# c12880ma.net
KiCad netlist of a schematic drawn in EAGLE
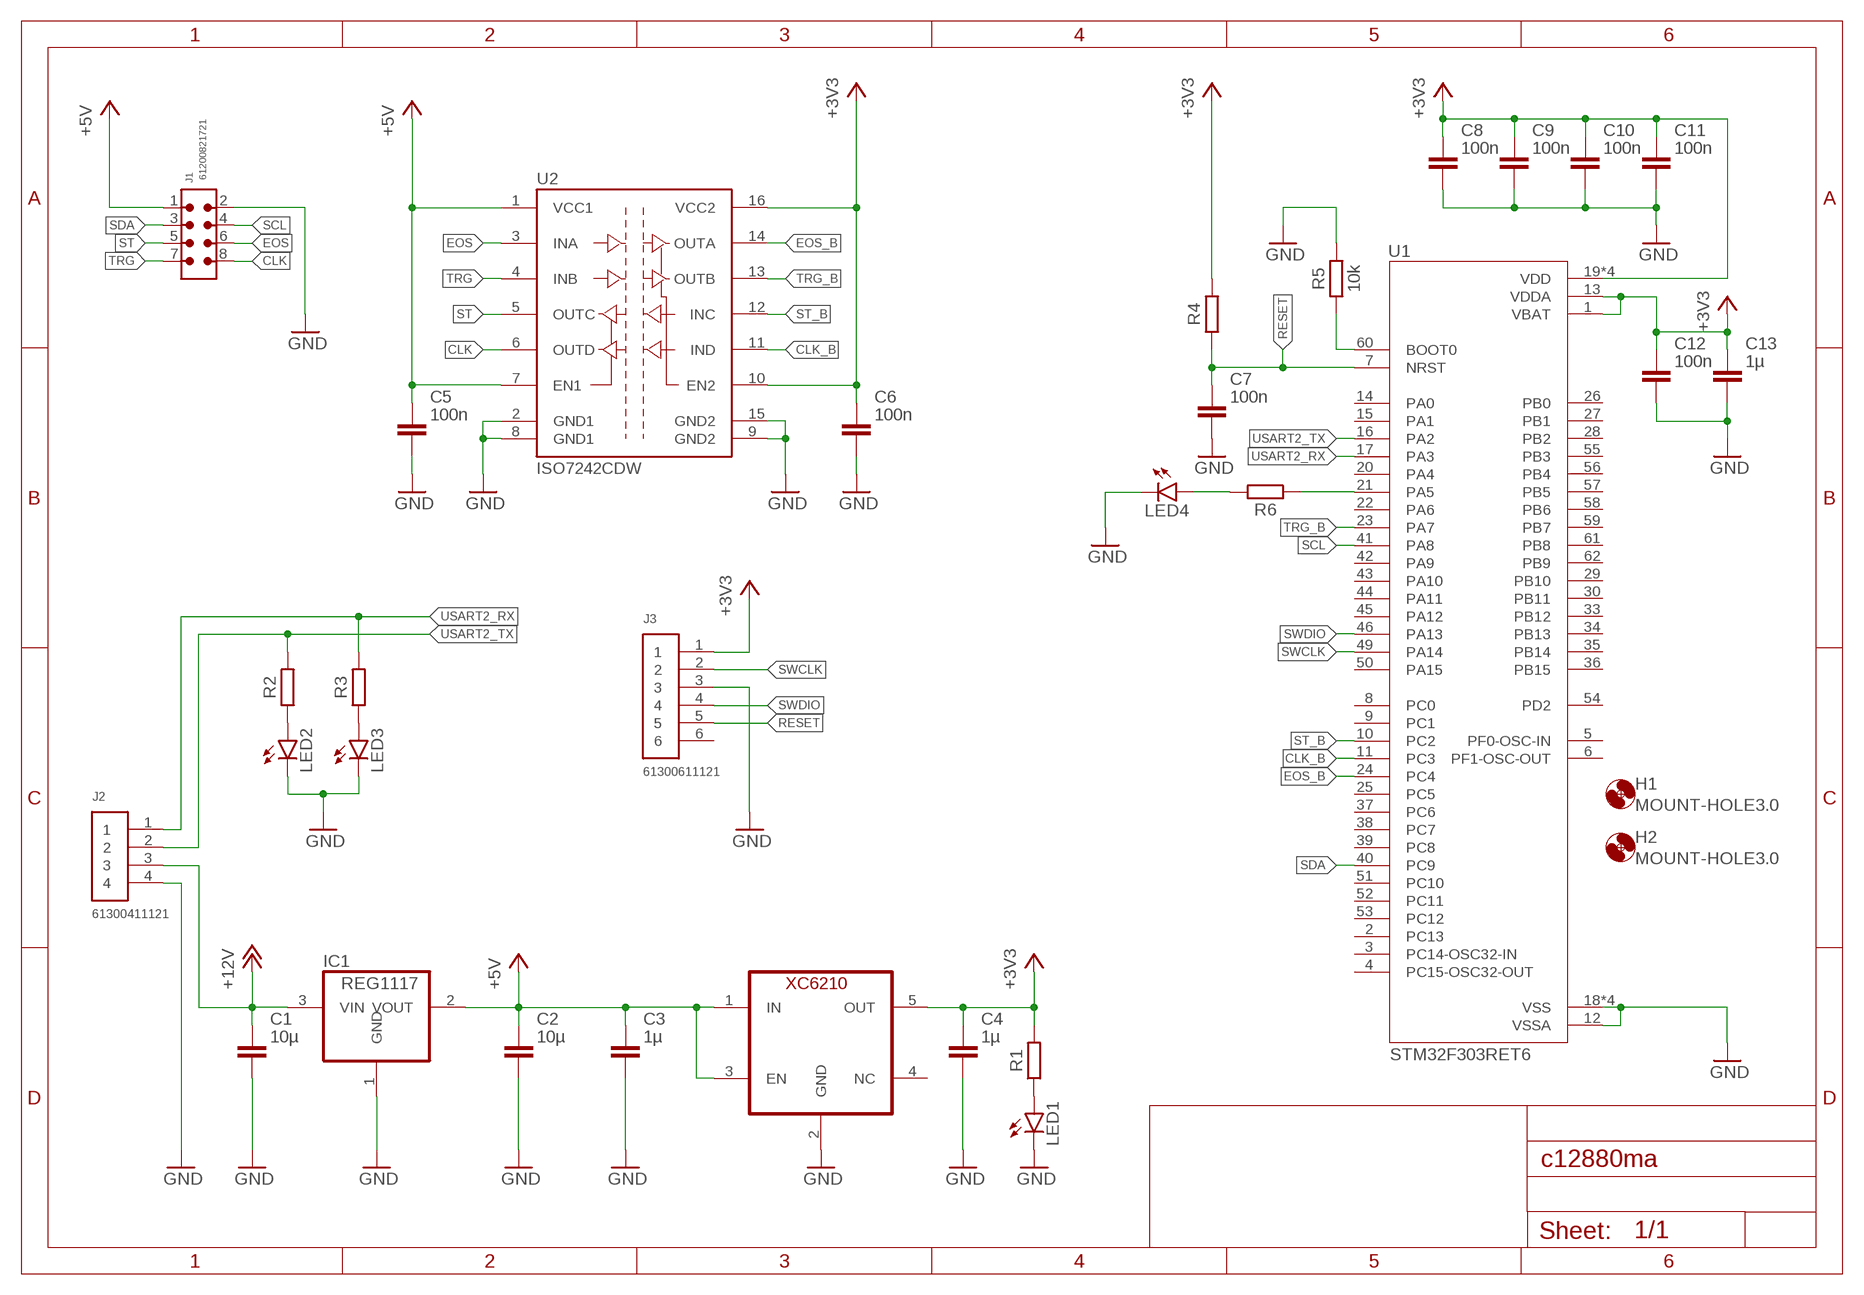
[diagram p0: schematic, sheet 1]

(export (version "E")
  (design (tool "Eeschema 10.0.6"))
  (components
    (comp (ref "C1")
      (value "10µ")
      (footprint "eagle-import:CAPC1608X85")
      (libsource (lib "eagle-import") (part "CCHIP-0603(1608-METRIC)_"))
    )
    (comp (ref "C2")
      (value "10µ")
      (footprint "eagle-import:CAPC1608X85")
      (libsource (lib "eagle-import") (part "CCHIP-0603(1608-METRIC)_"))
    )
    (comp (ref "C3")
      (value "1µ")
      (footprint "eagle-import:CAPC1608X85")
      (libsource (lib "eagle-import") (part "CCHIP-0603(1608-METRIC)_"))
    )
    (comp (ref "C4")
      (value "1µ")
      (footprint "eagle-import:CAPC1608X85")
      (libsource (lib "eagle-import") (part "CCHIP-0603(1608-METRIC)_"))
    )
    (comp (ref "C5")
      (value "100n")
      (footprint "eagle-import:CAPC1608X85")
      (libsource (lib "eagle-import") (part "CCHIP-0603(1608-METRIC)_"))
    )
    (comp (ref "C6")
      (value "100n")
      (footprint "eagle-import:CAPC1608X85")
      (libsource (lib "eagle-import") (part "CCHIP-0603(1608-METRIC)_"))
    )
    (comp (ref "C7")
      (value "100n")
      (footprint "eagle-import:CAPC1608X85")
      (libsource (lib "eagle-import") (part "CCHIP-0603(1608-METRIC)_"))
    )
    (comp (ref "C8")
      (value "100n")
      (footprint "eagle-import:CAPC1608X85")
      (libsource (lib "eagle-import") (part "CCHIP-0603(1608-METRIC)_"))
    )
    (comp (ref "C9")
      (value "100n")
      (footprint "eagle-import:CAPC1608X85")
      (libsource (lib "eagle-import") (part "CCHIP-0603(1608-METRIC)_"))
    )
    (comp (ref "C10")
      (value "100n")
      (footprint "eagle-import:CAPC1608X85")
      (libsource (lib "eagle-import") (part "CCHIP-0603(1608-METRIC)_"))
    )
    (comp (ref "C11")
      (value "100n")
      (footprint "eagle-import:CAPC1608X85")
      (libsource (lib "eagle-import") (part "CCHIP-0603(1608-METRIC)_"))
    )
    (comp (ref "C12")
      (value "100n")
      (footprint "eagle-import:CAPC1608X85")
      (libsource (lib "eagle-import") (part "CCHIP-0603(1608-METRIC)_"))
    )
    (comp (ref "C13")
      (value "1µ")
      (footprint "eagle-import:CAPC1608X85")
      (libsource (lib "eagle-import") (part "CCHIP-0603(1608-METRIC)_"))
    )
    (comp (ref "H1")
      (value "MOUNT-HOLE3.0")
      (footprint "eagle-import:3,0")
      (libsource (lib "eagle-import") (part "MOUNT-HOLE3.0"))
    )
    (comp (ref "H2")
      (value "MOUNT-HOLE3.0")
      (footprint "eagle-import:3,0")
      (libsource (lib "eagle-import") (part "MOUNT-HOLE3.0"))
    )
    (comp (ref "IC1")
      (value "REG1117")
      (footprint "eagle-import:SOT223")
      (libsource (lib "eagle-import") (part "REG1117"))
    )
    (comp (ref "J1")
      (value "61200821721")
      (footprint "eagle-import:61200821721")
      (libsource (lib "eagle-import") (part "6120XX21721_61200821721"))
    )
    (comp (ref "J2")
      (value "61300411121")
      (footprint "eagle-import:61300411121")
      (fields
        (field (name "DIGI_KEY_PART_NUMBER") "732-5317-ND")
        (field (name "MANUFACTURER") "Wurth Electronics Inc.")
        (field (name "CREATED_BY") "PCBLayout.com")
      )
      (libsource (lib "eagle-import") (part "61300411121"))
    )
    (comp (ref "J3")
      (value "61300611121")
      (footprint "eagle-import:61300611121")
      (fields
        (field (name "DIGI_KEY_PART_NUMBER") "732-5319-ND")
        (field (name "MANUFACTURER") "Wurth Electronics Inc.")
        (field (name "CREATED_BY") "PCBLayout.com")
      )
      (libsource (lib "eagle-import") (part "61300611121"))
    )
    (comp (ref "LED1")
      (value "LEDCHIP-LED0603")
      (footprint "eagle-import:CHIP-LED0603")
      (libsource (lib "eagle-import") (part "LEDCHIP-LED0603"))
    )
    (comp (ref "LED2")
      (value "LEDCHIP-LED0603")
      (footprint "eagle-import:CHIP-LED0603")
      (libsource (lib "eagle-import") (part "LEDCHIP-LED0603"))
    )
    (comp (ref "LED3")
      (value "LEDCHIP-LED0603")
      (footprint "eagle-import:CHIP-LED0603")
      (libsource (lib "eagle-import") (part "LEDCHIP-LED0603"))
    )
    (comp (ref "LED4")
      (value "LEDCHIP-LED0603")
      (footprint "eagle-import:CHIP-LED0603")
      (libsource (lib "eagle-import") (part "LEDCHIP-LED0603"))
    )
    (comp (ref "R1")
      (value "R_CHIP-0603(1608-METRIC)")
      (footprint "eagle-import:RESC1608X60")
      (libsource (lib "eagle-import") (part "RCHIP-0603(1608-METRIC)_"))
    )
    (comp (ref "R2")
      (value "R_CHIP-0603(1608-METRIC)")
      (footprint "eagle-import:RESC1608X60")
      (libsource (lib "eagle-import") (part "RCHIP-0603(1608-METRIC)_"))
    )
    (comp (ref "R3")
      (value "R_CHIP-0603(1608-METRIC)")
      (footprint "eagle-import:RESC1608X60")
      (libsource (lib "eagle-import") (part "RCHIP-0603(1608-METRIC)_"))
    )
    (comp (ref "R4")
      (value "R_CHIP-0603(1608-METRIC)")
      (footprint "eagle-import:RESC1608X60")
      (libsource (lib "eagle-import") (part "RCHIP-0603(1608-METRIC)_"))
    )
    (comp (ref "R5")
      (value "10k")
      (footprint "eagle-import:RESC1608X60")
      (libsource (lib "eagle-import") (part "RCHIP-0603(1608-METRIC)_"))
    )
    (comp (ref "R6")
      (value "R_CHIP-0603(1608-METRIC)")
      (footprint "eagle-import:RESC1608X60")
      (libsource (lib "eagle-import") (part "RCHIP-0603(1608-METRIC)_"))
    )
    (comp (ref "U$1")
      (value "XC6210")
      (footprint "eagle-import:SOT23-5")
      (libsource (lib "eagle-import") (part "XC6210"))
    )
    (comp (ref "U1")
      (value "STM32F303RET6")
      (footprint "eagle-import:QFP50P1200X1200X160-64N")
      (fields (field (name "MF") "STMicroelectronics"))
      (libsource (lib "eagle-import") (part "STM32F303RET6"))
    )
    (comp (ref "U2")
      (value "ISO7242CDW")
      (footprint "eagle-import:SO-16DW")
      (libsource (lib "eagle-import") (part "ISO7242DWC"))
    )
  )
  (nets
    (net (code "1") (name "+3V3") (class "Default")
      (node (ref "C10") (pin "1") (pinfunction "1_1") (pintype "passive"))
      (node (ref "C11") (pin "1") (pinfunction "1_1") (pintype "passive"))
      (node (ref "C12") (pin "1") (pinfunction "1_1") (pintype "passive"))
      (node (ref "C13") (pin "1") (pinfunction "1_1") (pintype "passive"))
      (node (ref "C4") (pin "1") (pinfunction "1_1") (pintype "passive"))
      (node (ref "C6") (pin "1") (pinfunction "1_1") (pintype "passive"))
      (node (ref "C8") (pin "1") (pinfunction "1_1") (pintype "passive"))
      (node (ref "C9") (pin "1") (pinfunction "1_1") (pintype "passive"))
      (node (ref "J3") (pin "1") (pinfunction "1_1") (pintype "passive"))
      (node (ref "R1") (pin "2") (pinfunction "2_2") (pintype "passive"))
      (node (ref "R4") (pin "2") (pinfunction "2_2") (pintype "passive"))
      (node (ref "U$1") (pin "5") (pinfunction "OUT_5") (pintype "bidirectional"))
      (node (ref "U1") (pin "1") (pinfunction "VBAT_1") (pintype "power_in"))
      (node (ref "U1") (pin "13") (pinfunction "VDDA_13") (pintype "power_in"))
      (node (ref "U1") (pin "19") (pinfunction "VDD_19") (pintype "power_in"))
      (node (ref "U1") (pin "32") (pinfunction "VDD_32") (pintype "power_in"))
      (node (ref "U1") (pin "48") (pinfunction "VDD_48") (pintype "power_in"))
      (node (ref "U1") (pin "64") (pinfunction "VDD_64") (pintype "power_in"))
      (node (ref "U2") (pin "10") (pinfunction "EN2_10") (pintype "passive"))
      (node (ref "U2") (pin "16") (pinfunction "VCC2_16") (pintype "power_in"))
    )
    (net (code "2") (name "+5V") (class "Default")
      (node (ref "C2") (pin "1") (pinfunction "1_1") (pintype "passive"))
      (node (ref "C3") (pin "1") (pinfunction "1_1") (pintype "passive"))
      (node (ref "C5") (pin "1") (pinfunction "1_1") (pintype "passive"))
      (node (ref "IC1") (pin "2") (pinfunction "VOUT_2") (pintype "output"))
      (node (ref "J1") (pin "1") (pinfunction "1_1") (pintype "passive"))
      (node (ref "U$1") (pin "1") (pinfunction "IN_1") (pintype "bidirectional"))
      (node (ref "U$1") (pin "3") (pinfunction "EN_3") (pintype "bidirectional"))
      (node (ref "U2") (pin "1") (pinfunction "VCC1_1") (pintype "power_in"))
      (node (ref "U2") (pin "7") (pinfunction "EN1_7") (pintype "passive"))
    )
    (net (code "3") (name "+12V") (class "Default")
      (node (ref "C1") (pin "1") (pinfunction "1_1") (pintype "passive"))
      (node (ref "IC1") (pin "3") (pinfunction "VIN_3") (pintype "input"))
      (node (ref "J2") (pin "3") (pinfunction "3_3") (pintype "passive"))
    )
    (net (code "4") (name "CLK") (class "Default")
      (node (ref "J1") (pin "8") (pinfunction "8_8") (pintype "passive"))
      (node (ref "U2") (pin "6") (pinfunction "OUTD_6") (pintype "tri_state"))
    )
    (net (code "5") (name "CLK_B") (class "Default")
      (node (ref "U1") (pin "11") (pinfunction "PC3_11") (pintype "bidirectional"))
      (node (ref "U2") (pin "11") (pinfunction "IND_11") (pintype "passive"))
    )
    (net (code "6") (name "EOS") (class "Default")
      (node (ref "J1") (pin "6") (pinfunction "6_6") (pintype "passive"))
      (node (ref "U2") (pin "3") (pinfunction "INA_3") (pintype "passive"))
    )
    (net (code "7") (name "EOS_B") (class "Default")
      (node (ref "U1") (pin "24") (pinfunction "PC4_24") (pintype "bidirectional"))
      (node (ref "U2") (pin "14") (pinfunction "OUTA_14") (pintype "tri_state"))
    )
    (net (code "8") (name "GND") (class "Default")
      (node (ref "C1") (pin "2") (pinfunction "2_2") (pintype "passive"))
      (node (ref "C10") (pin "2") (pinfunction "2_2") (pintype "passive"))
      (node (ref "C11") (pin "2") (pinfunction "2_2") (pintype "passive"))
      (node (ref "C12") (pin "2") (pinfunction "2_2") (pintype "passive"))
      (node (ref "C13") (pin "2") (pinfunction "2_2") (pintype "passive"))
      (node (ref "C2") (pin "2") (pinfunction "2_2") (pintype "passive"))
      (node (ref "C3") (pin "2") (pinfunction "2_2") (pintype "passive"))
      (node (ref "C4") (pin "2") (pinfunction "2_2") (pintype "passive"))
      (node (ref "C5") (pin "2") (pinfunction "2_2") (pintype "passive"))
      (node (ref "C6") (pin "2") (pinfunction "2_2") (pintype "passive"))
      (node (ref "C7") (pin "2") (pinfunction "2_2") (pintype "passive"))
      (node (ref "C8") (pin "2") (pinfunction "2_2") (pintype "passive"))
      (node (ref "C9") (pin "2") (pinfunction "2_2") (pintype "passive"))
      (node (ref "IC1") (pin "1") (pinfunction "GND_1") (pintype "power_in"))
      (node (ref "J1") (pin "2") (pinfunction "2_2") (pintype "passive"))
      (node (ref "J2") (pin "4") (pinfunction "4_4") (pintype "passive"))
      (node (ref "J3") (pin "3") (pinfunction "3_3") (pintype "passive"))
      (node (ref "LED1") (pin "C") (pinfunction "C_C") (pintype "passive"))
      (node (ref "LED2") (pin "C") (pinfunction "C_C") (pintype "passive"))
      (node (ref "LED3") (pin "C") (pinfunction "C_C") (pintype "passive"))
      (node (ref "LED4") (pin "C") (pinfunction "C_C") (pintype "passive"))
      (node (ref "R5") (pin "2") (pinfunction "2_2") (pintype "passive"))
      (node (ref "U$1") (pin "2") (pinfunction "GND_2") (pintype "bidirectional"))
      (node (ref "U1") (pin "12") (pinfunction "VSSA_12") (pintype "power_in"))
      (node (ref "U1") (pin "18") (pinfunction "VSS_18") (pintype "power_in"))
      (node (ref "U1") (pin "31") (pinfunction "VSS_31") (pintype "power_in"))
      (node (ref "U1") (pin "47") (pinfunction "VSS_47") (pintype "power_in"))
      (node (ref "U1") (pin "63") (pinfunction "VSS_63") (pintype "power_in"))
      (node (ref "U2") (pin "15") (pinfunction "GND2_15") (pintype "power_in"))
      (node (ref "U2") (pin "2") (pinfunction "GND1_2") (pintype "power_in"))
      (node (ref "U2") (pin "8") (pinfunction "GND1_8") (pintype "power_in"))
      (node (ref "U2") (pin "9") (pinfunction "GND2_9") (pintype "power_in"))
    )
    (net (code "9") (name "Net-(LED1-PadA)") (class "Default")
      (node (ref "LED1") (pin "A") (pinfunction "A_A") (pintype "passive"))
      (node (ref "R1") (pin "1") (pinfunction "1_1") (pintype "passive"))
    )
    (net (code "10") (name "Net-(LED2-PadA)") (class "Default")
      (node (ref "LED2") (pin "A") (pinfunction "A_A") (pintype "passive"))
      (node (ref "R2") (pin "1") (pinfunction "1_1") (pintype "passive"))
    )
    (net (code "11") (name "Net-(LED3-PadA)") (class "Default")
      (node (ref "LED3") (pin "A") (pinfunction "A_A") (pintype "passive"))
      (node (ref "R3") (pin "1") (pinfunction "1_1") (pintype "passive"))
    )
    (net (code "12") (name "Net-(LED4-PadA)") (class "Default")
      (node (ref "LED4") (pin "A") (pinfunction "A_A") (pintype "passive"))
      (node (ref "R6") (pin "2") (pinfunction "2_2") (pintype "passive"))
    )
    (net (code "13") (name "Net-(U1-BOOT0)") (class "Default")
      (node (ref "R5") (pin "1") (pinfunction "1_1") (pintype "passive"))
      (node (ref "U1") (pin "60") (pinfunction "BOOT0_60") (pintype "input"))
    )
    (net (code "14") (name "Net-(U1-PA5)") (class "Default")
      (node (ref "R6") (pin "1") (pinfunction "1_1") (pintype "passive"))
      (node (ref "U1") (pin "21") (pinfunction "PA5_21") (pintype "bidirectional"))
    )
    (net (code "15") (name "RESET") (class "Default")
      (node (ref "C7") (pin "1") (pinfunction "1_1") (pintype "passive"))
      (node (ref "J3") (pin "5") (pinfunction "5_5") (pintype "passive"))
      (node (ref "R4") (pin "1") (pinfunction "1_1") (pintype "passive"))
      (node (ref "U1") (pin "7") (pinfunction "NRST_7") (pintype "bidirectional"))
    )
    (net (code "16") (name "SCL") (class "Default")
      (node (ref "J1") (pin "4") (pinfunction "4_4") (pintype "passive"))
      (node (ref "U1") (pin "41") (pinfunction "PA8_41") (pintype "bidirectional"))
    )
    (net (code "17") (name "SDA") (class "Default")
      (node (ref "J1") (pin "3") (pinfunction "3_3") (pintype "passive"))
      (node (ref "U1") (pin "40") (pinfunction "PC9_40") (pintype "bidirectional"))
    )
    (net (code "18") (name "ST") (class "Default")
      (node (ref "J1") (pin "5") (pinfunction "5_5") (pintype "passive"))
      (node (ref "U2") (pin "5") (pinfunction "OUTC_5") (pintype "tri_state"))
    )
    (net (code "19") (name "ST_B") (class "Default")
      (node (ref "U1") (pin "10") (pinfunction "PC2_10") (pintype "bidirectional"))
      (node (ref "U2") (pin "12") (pinfunction "INC_12") (pintype "passive"))
    )
    (net (code "20") (name "SWCLK") (class "Default")
      (node (ref "J3") (pin "2") (pinfunction "2_2") (pintype "passive"))
      (node (ref "U1") (pin "49") (pinfunction "PA14_49") (pintype "bidirectional"))
    )
    (net (code "21") (name "SWDIO") (class "Default")
      (node (ref "J3") (pin "4") (pinfunction "4_4") (pintype "passive"))
      (node (ref "U1") (pin "46") (pinfunction "PA13_46") (pintype "bidirectional"))
    )
    (net (code "22") (name "TRG") (class "Default")
      (node (ref "J1") (pin "7") (pinfunction "7_7") (pintype "passive"))
      (node (ref "U2") (pin "4") (pinfunction "INB_4") (pintype "passive"))
    )
    (net (code "23") (name "TRG_B") (class "Default")
      (node (ref "U1") (pin "23") (pinfunction "PA7_23") (pintype "bidirectional"))
      (node (ref "U2") (pin "13") (pinfunction "OUTB_13") (pintype "tri_state"))
    )
    (net (code "24") (name "USART2_RX") (class "Default")
      (node (ref "J2") (pin "1") (pinfunction "1_1") (pintype "passive"))
      (node (ref "R3") (pin "2") (pinfunction "2_2") (pintype "passive"))
      (node (ref "U1") (pin "17") (pinfunction "PA3_17") (pintype "bidirectional"))
    )
    (net (code "25") (name "USART2_TX") (class "Default")
      (node (ref "J2") (pin "2") (pinfunction "2_2") (pintype "passive"))
      (node (ref "R2") (pin "2") (pinfunction "2_2") (pintype "passive"))
      (node (ref "U1") (pin "16") (pinfunction "PA2_16") (pintype "bidirectional"))
    )
    (net (code "26") (name "unconnected-(J3-Pad6)") (class "Default")
      (node (ref "J3") (pin "6") (pinfunction "6_6") (pintype "passive"))
    )
    (net (code "27") (name "unconnected-(U$1-NC-Pad4)") (class "Default")
      (node (ref "U$1") (pin "4") (pinfunction "NC_4") (pintype "bidirectional"))
    )
    (net (code "28") (name "unconnected-(U1-PA0-Pad14)") (class "Default")
      (node (ref "U1") (pin "14") (pinfunction "PA0_14") (pintype "bidirectional"))
    )
    (net (code "29") (name "unconnected-(U1-PA1-Pad15)") (class "Default")
      (node (ref "U1") (pin "15") (pinfunction "PA1_15") (pintype "bidirectional"))
    )
    (net (code "30") (name "unconnected-(U1-PA4-Pad20)") (class "Default")
      (node (ref "U1") (pin "20") (pinfunction "PA4_20") (pintype "bidirectional"))
    )
    (net (code "31") (name "unconnected-(U1-PA6-Pad22)") (class "Default")
      (node (ref "U1") (pin "22") (pinfunction "PA6_22") (pintype "bidirectional"))
    )
    (net (code "32") (name "unconnected-(U1-PA9-Pad42)") (class "Default")
      (node (ref "U1") (pin "42") (pinfunction "PA9_42") (pintype "bidirectional"))
    )
    (net (code "33") (name "unconnected-(U1-PA10-Pad43)") (class "Default")
      (node (ref "U1") (pin "43") (pinfunction "PA10_43") (pintype "bidirectional"))
    )
    (net (code "34") (name "unconnected-(U1-PA11-Pad44)") (class "Default")
      (node (ref "U1") (pin "44") (pinfunction "PA11_44") (pintype "bidirectional"))
    )
    (net (code "35") (name "unconnected-(U1-PA12-Pad45)") (class "Default")
      (node (ref "U1") (pin "45") (pinfunction "PA12_45") (pintype "bidirectional"))
    )
    (net (code "36") (name "unconnected-(U1-PA15-Pad50)") (class "Default")
      (node (ref "U1") (pin "50") (pinfunction "PA15_50") (pintype "bidirectional"))
    )
    (net (code "37") (name "unconnected-(U1-PB0-Pad26)") (class "Default")
      (node (ref "U1") (pin "26") (pinfunction "PB0_26") (pintype "bidirectional"))
    )
    (net (code "38") (name "unconnected-(U1-PB1-Pad27)") (class "Default")
      (node (ref "U1") (pin "27") (pinfunction "PB1_27") (pintype "bidirectional"))
    )
    (net (code "39") (name "unconnected-(U1-PB2-Pad28)") (class "Default")
      (node (ref "U1") (pin "28") (pinfunction "PB2_28") (pintype "bidirectional"))
    )
    (net (code "40") (name "unconnected-(U1-PB3-Pad55)") (class "Default")
      (node (ref "U1") (pin "55") (pinfunction "PB3_55") (pintype "bidirectional"))
    )
    (net (code "41") (name "unconnected-(U1-PB4-Pad56)") (class "Default")
      (node (ref "U1") (pin "56") (pinfunction "PB4_56") (pintype "bidirectional"))
    )
    (net (code "42") (name "unconnected-(U1-PB5-Pad57)") (class "Default")
      (node (ref "U1") (pin "57") (pinfunction "PB5_57") (pintype "bidirectional"))
    )
    (net (code "43") (name "unconnected-(U1-PB6-Pad58)") (class "Default")
      (node (ref "U1") (pin "58") (pinfunction "PB6_58") (pintype "bidirectional"))
    )
    (net (code "44") (name "unconnected-(U1-PB7-Pad59)") (class "Default")
      (node (ref "U1") (pin "59") (pinfunction "PB7_59") (pintype "bidirectional"))
    )
    (net (code "45") (name "unconnected-(U1-PB8-Pad61)") (class "Default")
      (node (ref "U1") (pin "61") (pinfunction "PB8_61") (pintype "bidirectional"))
    )
    (net (code "46") (name "unconnected-(U1-PB9-Pad62)") (class "Default")
      (node (ref "U1") (pin "62") (pinfunction "PB9_62") (pintype "bidirectional"))
    )
    (net (code "47") (name "unconnected-(U1-PB10-Pad29)") (class "Default")
      (node (ref "U1") (pin "29") (pinfunction "PB10_29") (pintype "bidirectional"))
    )
    (net (code "48") (name "unconnected-(U1-PB11-Pad30)") (class "Default")
      (node (ref "U1") (pin "30") (pinfunction "PB11_30") (pintype "bidirectional"))
    )
    (net (code "49") (name "unconnected-(U1-PB12-Pad33)") (class "Default")
      (node (ref "U1") (pin "33") (pinfunction "PB12_33") (pintype "bidirectional"))
    )
    (net (code "50") (name "unconnected-(U1-PB13-Pad34)") (class "Default")
      (node (ref "U1") (pin "34") (pinfunction "PB13_34") (pintype "bidirectional"))
    )
    (net (code "51") (name "unconnected-(U1-PB14-Pad35)") (class "Default")
      (node (ref "U1") (pin "35") (pinfunction "PB14_35") (pintype "bidirectional"))
    )
    (net (code "52") (name "unconnected-(U1-PB15-Pad36)") (class "Default")
      (node (ref "U1") (pin "36") (pinfunction "PB15_36") (pintype "bidirectional"))
    )
    (net (code "53") (name "unconnected-(U1-PC0-Pad8)") (class "Default")
      (node (ref "U1") (pin "8") (pinfunction "PC0_8") (pintype "bidirectional"))
    )
    (net (code "54") (name "unconnected-(U1-PC1-Pad9)") (class "Default")
      (node (ref "U1") (pin "9") (pinfunction "PC1_9") (pintype "bidirectional"))
    )
    (net (code "55") (name "unconnected-(U1-PC5-Pad25)") (class "Default")
      (node (ref "U1") (pin "25") (pinfunction "PC5_25") (pintype "bidirectional"))
    )
    (net (code "56") (name "unconnected-(U1-PC6-Pad37)") (class "Default")
      (node (ref "U1") (pin "37") (pinfunction "PC6_37") (pintype "bidirectional"))
    )
    (net (code "57") (name "unconnected-(U1-PC7-Pad38)") (class "Default")
      (node (ref "U1") (pin "38") (pinfunction "PC7_38") (pintype "bidirectional"))
    )
    (net (code "58") (name "unconnected-(U1-PC8-Pad39)") (class "Default")
      (node (ref "U1") (pin "39") (pinfunction "PC8_39") (pintype "bidirectional"))
    )
    (net (code "59") (name "unconnected-(U1-PC10-Pad51)") (class "Default")
      (node (ref "U1") (pin "51") (pinfunction "PC10_51") (pintype "bidirectional"))
    )
    (net (code "60") (name "unconnected-(U1-PC11-Pad52)") (class "Default")
      (node (ref "U1") (pin "52") (pinfunction "PC11_52") (pintype "bidirectional"))
    )
    (net (code "61") (name "unconnected-(U1-PC12-Pad53)") (class "Default")
      (node (ref "U1") (pin "53") (pinfunction "PC12_53") (pintype "bidirectional"))
    )
    (net (code "62") (name "unconnected-(U1-PC13-Pad2)") (class "Default")
      (node (ref "U1") (pin "2") (pinfunction "PC13_2") (pintype "bidirectional"))
    )
    (net (code "63") (name "unconnected-(U1-PC14-OSC32-IN-Pad3)") (class "Default")
      (node (ref "U1") (pin "3") (pinfunction "PC14-OSC32-IN_3") (pintype "bidirectional"))
    )
    (net (code "64") (name "unconnected-(U1-PC15-OSC32-OUT-Pad4)") (class "Default")
      (node (ref "U1") (pin "4") (pinfunction "PC15-OSC32-OUT_4") (pintype "bidirectional"))
    )
    (net (code "65") (name "unconnected-(U1-PD2-Pad54)") (class "Default")
      (node (ref "U1") (pin "54") (pinfunction "PD2_54") (pintype "bidirectional"))
    )
    (net (code "66") (name "unconnected-(U1-PF0-OSC-IN-Pad5)") (class "Default")
      (node (ref "U1") (pin "5") (pinfunction "PF0-OSC-IN_5") (pintype "bidirectional"))
    )
    (net (code "67") (name "unconnected-(U1-PF1-OSC-OUT-Pad6)") (class "Default")
      (node (ref "U1") (pin "6") (pinfunction "PF1-OSC-OUT_6") (pintype "bidirectional"))
    )
  )
)
